# FeatherProto-V2_0.net
KiCad netlist of a schematic drawn in EAGLE
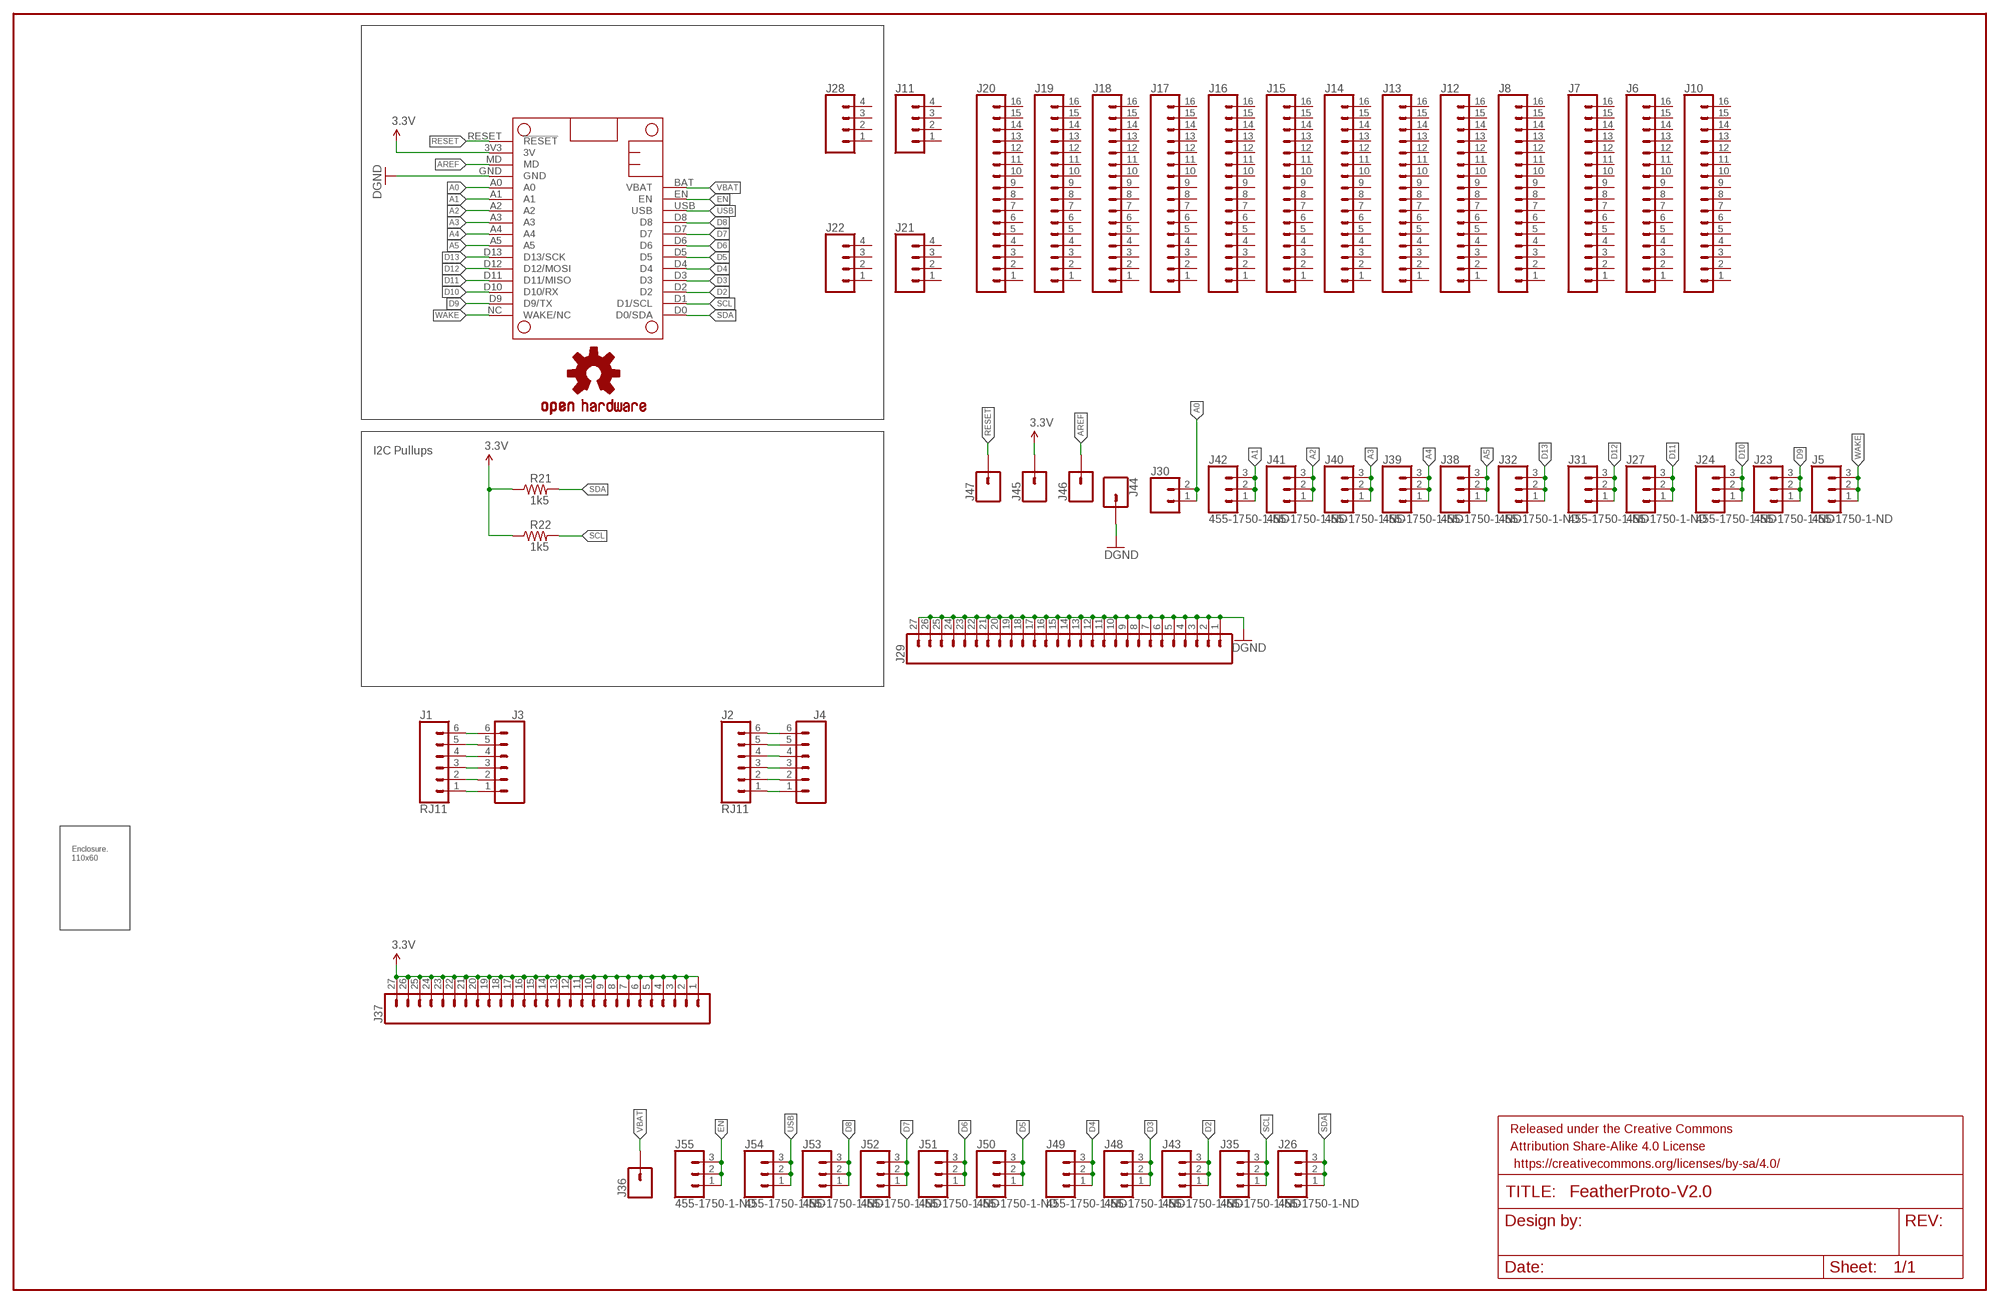
[diagram p0: schematic, sheet 1]

(export (version "E")
  (design (tool "Eeschema 10.0.6"))
  (components
    (comp (ref "FRAME2")
      (value "FRAME-LEDGER")
      (footprint "eagle-import:CREATIVE_COMMONS")
      (libsource (lib "eagle-import") (part "FRAME-LEDGER"))
    )
    (comp (ref "J1")
      (value "RJ11")
      (footprint "eagle-import:RJ11-6")
      (libsource (lib "eagle-import") (part "RJ11-6"))
    )
    (comp (ref "J2")
      (value "RJ11")
      (footprint "eagle-import:RJ11-6")
      (libsource (lib "eagle-import") (part "RJ11-6"))
    )
    (comp (ref "J3")
      (value "CONN_06SILK_FEMALE_PTH")
      (footprint "eagle-import:1X06")
      (libsource (lib "eagle-import") (part "CONN_06SILK_FEMALE_PTH"))
    )
    (comp (ref "J4")
      (value "CONN_06SILK_FEMALE_PTH")
      (footprint "eagle-import:1X06")
      (libsource (lib "eagle-import") (part "CONN_06SILK_FEMALE_PTH"))
    )
    (comp (ref "J5")
      (value "455-1750-1-ND")
      (footprint "eagle-import:1X03")
      (libsource (lib "eagle-import") (part "CONN_03"))
    )
    (comp (ref "J6")
      (value "CONN_161X16_NO_SILK")
      (footprint "eagle-import:1X16_NO_SILK")
      (libsource (lib "eagle-import") (part "CONN_161X16_NO_SILK"))
    )
    (comp (ref "J7")
      (value "CONN_161X16_NO_SILK")
      (footprint "eagle-import:1X16_NO_SILK")
      (libsource (lib "eagle-import") (part "CONN_161X16_NO_SILK"))
    )
    (comp (ref "J8")
      (value "CONN_161X16_NO_SILK")
      (footprint "eagle-import:1X16_NO_SILK")
      (libsource (lib "eagle-import") (part "CONN_161X16_NO_SILK"))
    )
    (comp (ref "J10")
      (value "CONN_161X16_NO_SILK")
      (footprint "eagle-import:1X16_NO_SILK")
      (libsource (lib "eagle-import") (part "CONN_161X16_NO_SILK"))
    )
    (comp (ref "J11")
      (value "CONN_041X04_NO_SILK")
      (footprint "eagle-import:1X04_NO_SILK")
      (libsource (lib "eagle-import") (part "CONN_041X04_NO_SILK"))
    )
    (comp (ref "J12")
      (value "CONN_161X16_NO_SILK")
      (footprint "eagle-import:1X16_NO_SILK")
      (libsource (lib "eagle-import") (part "CONN_161X16_NO_SILK"))
    )
    (comp (ref "J13")
      (value "CONN_161X16_NO_SILK")
      (footprint "eagle-import:1X16_NO_SILK")
      (libsource (lib "eagle-import") (part "CONN_161X16_NO_SILK"))
    )
    (comp (ref "J14")
      (value "CONN_161X16_NO_SILK")
      (footprint "eagle-import:1X16_NO_SILK")
      (libsource (lib "eagle-import") (part "CONN_161X16_NO_SILK"))
    )
    (comp (ref "J15")
      (value "CONN_161X16_NO_SILK")
      (footprint "eagle-import:1X16_NO_SILK")
      (libsource (lib "eagle-import") (part "CONN_161X16_NO_SILK"))
    )
    (comp (ref "J16")
      (value "CONN_161X16_NO_SILK")
      (footprint "eagle-import:1X16_NO_SILK")
      (libsource (lib "eagle-import") (part "CONN_161X16_NO_SILK"))
    )
    (comp (ref "J17")
      (value "CONN_161X16_NO_SILK")
      (footprint "eagle-import:1X16_NO_SILK")
      (libsource (lib "eagle-import") (part "CONN_161X16_NO_SILK"))
    )
    (comp (ref "J18")
      (value "CONN_161X16_NO_SILK")
      (footprint "eagle-import:1X16_NO_SILK")
      (libsource (lib "eagle-import") (part "CONN_161X16_NO_SILK"))
    )
    (comp (ref "J19")
      (value "CONN_161X16_NO_SILK")
      (footprint "eagle-import:1X16_NO_SILK")
      (libsource (lib "eagle-import") (part "CONN_161X16_NO_SILK"))
    )
    (comp (ref "J20")
      (value "CONN_161X16_NO_SILK")
      (footprint "eagle-import:1X16_NO_SILK")
      (libsource (lib "eagle-import") (part "CONN_161X16_NO_SILK"))
    )
    (comp (ref "J21")
      (value "CONN_041X04_NO_SILK")
      (footprint "eagle-import:1X04_NO_SILK")
      (libsource (lib "eagle-import") (part "CONN_041X04_NO_SILK"))
    )
    (comp (ref "J22")
      (value "CONN_041X04_NO_SILK")
      (footprint "eagle-import:1X04_NO_SILK")
      (libsource (lib "eagle-import") (part "CONN_041X04_NO_SILK"))
    )
    (comp (ref "J23")
      (value "455-1750-1-ND")
      (footprint "eagle-import:1X03")
      (libsource (lib "eagle-import") (part "CONN_03"))
    )
    (comp (ref "J24")
      (value "455-1750-1-ND")
      (footprint "eagle-import:1X03")
      (libsource (lib "eagle-import") (part "CONN_03"))
    )
    (comp (ref "J26")
      (value "455-1750-1-ND")
      (footprint "eagle-import:1X03")
      (libsource (lib "eagle-import") (part "CONN_03"))
    )
    (comp (ref "J27")
      (value "455-1750-1-ND")
      (footprint "eagle-import:1X03")
      (libsource (lib "eagle-import") (part "CONN_03"))
    )
    (comp (ref "J28")
      (value "CONN_041X04_NO_SILK")
      (footprint "eagle-import:1X04_NO_SILK")
      (libsource (lib "eagle-import") (part "CONN_041X04_NO_SILK"))
    )
    (comp (ref "J29")
      (value "CONN_27")
      (footprint "eagle-import:1X27")
      (libsource (lib "eagle-import") (part "CONN_27"))
    )
    (comp (ref "J30")
      (value "CONN_02")
      (footprint "eagle-import:1X02")
      (libsource (lib "eagle-import") (part "CONN_02"))
    )
    (comp (ref "J31")
      (value "455-1750-1-ND")
      (footprint "eagle-import:1X03")
      (libsource (lib "eagle-import") (part "CONN_03"))
    )
    (comp (ref "J32")
      (value "455-1750-1-ND")
      (footprint "eagle-import:1X03")
      (libsource (lib "eagle-import") (part "CONN_03"))
    )
    (comp (ref "J35")
      (value "455-1750-1-ND")
      (footprint "eagle-import:1X03")
      (libsource (lib "eagle-import") (part "CONN_03"))
    )
    (comp (ref "J36")
      (value "CONN_01PTH_NO_SILK_YES_STOP")
      (footprint "eagle-import:1X01_NO_SILK")
      (libsource (lib "eagle-import") (part "CONN_01PTH_NO_SILK_YES_STOP"))
    )
    (comp (ref "J37")
      (value "CONN_27")
      (footprint "eagle-import:1X27")
      (libsource (lib "eagle-import") (part "CONN_27"))
    )
    (comp (ref "J38")
      (value "455-1750-1-ND")
      (footprint "eagle-import:1X03")
      (libsource (lib "eagle-import") (part "CONN_03"))
    )
    (comp (ref "J39")
      (value "455-1750-1-ND")
      (footprint "eagle-import:1X03")
      (libsource (lib "eagle-import") (part "CONN_03"))
    )
    (comp (ref "J40")
      (value "455-1750-1-ND")
      (footprint "eagle-import:1X03")
      (libsource (lib "eagle-import") (part "CONN_03"))
    )
    (comp (ref "J41")
      (value "455-1750-1-ND")
      (footprint "eagle-import:1X03")
      (libsource (lib "eagle-import") (part "CONN_03"))
    )
    (comp (ref "J42")
      (value "455-1750-1-ND")
      (footprint "eagle-import:1X03")
      (libsource (lib "eagle-import") (part "CONN_03"))
    )
    (comp (ref "J43")
      (value "455-1750-1-ND")
      (footprint "eagle-import:1X03")
      (libsource (lib "eagle-import") (part "CONN_03"))
    )
    (comp (ref "J44")
      (value "CONN_01PTH_NO_SILK_YES_STOP")
      (footprint "eagle-import:1X01_NO_SILK")
      (libsource (lib "eagle-import") (part "CONN_01PTH_NO_SILK_YES_STOP"))
    )
    (comp (ref "J45")
      (value "CONN_01PTH_NO_SILK_YES_STOP")
      (footprint "eagle-import:1X01_NO_SILK")
      (libsource (lib "eagle-import") (part "CONN_01PTH_NO_SILK_YES_STOP"))
    )
    (comp (ref "J46")
      (value "CONN_01PTH_NO_SILK_YES_STOP")
      (footprint "eagle-import:1X01_NO_SILK")
      (libsource (lib "eagle-import") (part "CONN_01PTH_NO_SILK_YES_STOP"))
    )
    (comp (ref "J47")
      (value "CONN_01PTH_NO_SILK_YES_STOP")
      (footprint "eagle-import:1X01_NO_SILK")
      (libsource (lib "eagle-import") (part "CONN_01PTH_NO_SILK_YES_STOP"))
    )
    (comp (ref "J48")
      (value "455-1750-1-ND")
      (footprint "eagle-import:1X03")
      (libsource (lib "eagle-import") (part "CONN_03"))
    )
    (comp (ref "J49")
      (value "455-1750-1-ND")
      (footprint "eagle-import:1X03")
      (libsource (lib "eagle-import") (part "CONN_03"))
    )
    (comp (ref "J50")
      (value "455-1750-1-ND")
      (footprint "eagle-import:1X03")
      (libsource (lib "eagle-import") (part "CONN_03"))
    )
    (comp (ref "J51")
      (value "455-1750-1-ND")
      (footprint "eagle-import:1X03")
      (libsource (lib "eagle-import") (part "CONN_03"))
    )
    (comp (ref "J52")
      (value "455-1750-1-ND")
      (footprint "eagle-import:1X03")
      (libsource (lib "eagle-import") (part "CONN_03"))
    )
    (comp (ref "J53")
      (value "455-1750-1-ND")
      (footprint "eagle-import:1X03")
      (libsource (lib "eagle-import") (part "CONN_03"))
    )
    (comp (ref "J54")
      (value "455-1750-1-ND")
      (footprint "eagle-import:1X03")
      (libsource (lib "eagle-import") (part "CONN_03"))
    )
    (comp (ref "J55")
      (value "455-1750-1-ND")
      (footprint "eagle-import:1X03")
      (libsource (lib "eagle-import") (part "CONN_03"))
    )
    (comp (ref "LOGO1")
      (value "OSHW-LOGOM")
      (footprint "eagle-import:OSHW-LOGO-M")
      (libsource (lib "eagle-import") (part "OSHW-LOGOM"))
    )
    (comp (ref "MS1")
      (value "XENONA")
      (footprint "eagle-import:XENON_BREAKOUT_A")
      (libsource (lib "eagle-import") (part "XENONA"))
    )
    (comp (ref "R21")
      (value "1k5")
      (footprint "eagle-import:0805")
      (libsource (lib "eagle-import") (part "RESISTOR0805"))
    )
    (comp (ref "R22")
      (value "1k5")
      (footprint "eagle-import:0805")
      (libsource (lib "eagle-import") (part "RESISTOR0805"))
    )
    (comp (ref "U$1")
      (value "CAMDENBOSS-ENCLOSURE-110X60BOTH-EXTENDED-WIDE")
      (footprint "eagle-import:CAMDENBOSS_ENCLOSURE_110X60_WIDE_EXTENDED")
      (libsource (lib "eagle-import") (part "CAMDENBOSS-ENCLOSURE-110X60BOTH-EXTENDED-WIDE"))
    )
  )
  (nets
    (net (code "1") (name "3.3V") (class "Default")
      (node (ref "J37") (pin "1") (pinfunction "1_1") (pintype "passive"))
      (node (ref "J37") (pin "10") (pinfunction "10_10") (pintype "passive"))
      (node (ref "J37") (pin "11") (pinfunction "11_11") (pintype "passive"))
      (node (ref "J37") (pin "12") (pinfunction "12_12") (pintype "passive"))
      (node (ref "J37") (pin "13") (pinfunction "13_13") (pintype "passive"))
      (node (ref "J37") (pin "14") (pinfunction "14_14") (pintype "passive"))
      (node (ref "J37") (pin "15") (pinfunction "15_15") (pintype "passive"))
      (node (ref "J37") (pin "16") (pinfunction "16_16") (pintype "passive"))
      (node (ref "J37") (pin "17") (pinfunction "17_17") (pintype "passive"))
      (node (ref "J37") (pin "18") (pinfunction "18_18") (pintype "passive"))
      (node (ref "J37") (pin "19") (pinfunction "19_19") (pintype "passive"))
      (node (ref "J37") (pin "2") (pinfunction "2_2") (pintype "passive"))
      (node (ref "J37") (pin "20") (pinfunction "20_20") (pintype "passive"))
      (node (ref "J37") (pin "21") (pinfunction "21_21") (pintype "passive"))
      (node (ref "J37") (pin "22") (pinfunction "22_22") (pintype "passive"))
      (node (ref "J37") (pin "23") (pinfunction "23_23") (pintype "passive"))
      (node (ref "J37") (pin "24") (pinfunction "24_24") (pintype "passive"))
      (node (ref "J37") (pin "25") (pinfunction "25_25") (pintype "passive"))
      (node (ref "J37") (pin "26") (pinfunction "26_26") (pintype "passive"))
      (node (ref "J37") (pin "27") (pinfunction "27_27") (pintype "passive"))
      (node (ref "J37") (pin "3") (pinfunction "3_3") (pintype "passive"))
      (node (ref "J37") (pin "4") (pinfunction "4_4") (pintype "passive"))
      (node (ref "J37") (pin "5") (pinfunction "5_5") (pintype "passive"))
      (node (ref "J37") (pin "6") (pinfunction "6_6") (pintype "passive"))
      (node (ref "J37") (pin "7") (pinfunction "7_7") (pintype "passive"))
      (node (ref "J37") (pin "8") (pinfunction "8_8") (pintype "passive"))
      (node (ref "J37") (pin "9") (pinfunction "9_9") (pintype "passive"))
      (node (ref "J45") (pin "1") (pinfunction "1_1") (pintype "passive"))
      (node (ref "MS1") (pin "3V3") (pinfunction "3V_3V3") (pintype "power_in"))
      (node (ref "R21") (pin "1") (pinfunction "1_1") (pintype "passive"))
      (node (ref "R22") (pin "1") (pinfunction "1_1") (pintype "passive"))
    )
    (net (code "2") (name "A0") (class "Default")
      (node (ref "J30") (pin "1") (pinfunction "1_1") (pintype "passive"))
      (node (ref "J30") (pin "2") (pinfunction "2_2") (pintype "passive"))
      (node (ref "MS1") (pin "A0") (pinfunction "A0_A0") (pintype "bidirectional"))
    )
    (net (code "3") (name "A1") (class "Default")
      (node (ref "J42") (pin "1") (pinfunction "1_1") (pintype "passive"))
      (node (ref "J42") (pin "2") (pinfunction "2_2") (pintype "passive"))
      (node (ref "J42") (pin "3") (pinfunction "3_3") (pintype "passive"))
      (node (ref "MS1") (pin "A1") (pinfunction "A1_A1") (pintype "bidirectional"))
    )
    (net (code "4") (name "A2") (class "Default")
      (node (ref "J41") (pin "1") (pinfunction "1_1") (pintype "passive"))
      (node (ref "J41") (pin "2") (pinfunction "2_2") (pintype "passive"))
      (node (ref "J41") (pin "3") (pinfunction "3_3") (pintype "passive"))
      (node (ref "MS1") (pin "A2") (pinfunction "A2_A2") (pintype "bidirectional"))
    )
    (net (code "5") (name "A3") (class "Default")
      (node (ref "J40") (pin "1") (pinfunction "1_1") (pintype "passive"))
      (node (ref "J40") (pin "2") (pinfunction "2_2") (pintype "passive"))
      (node (ref "J40") (pin "3") (pinfunction "3_3") (pintype "passive"))
      (node (ref "MS1") (pin "A3") (pinfunction "A3_A3") (pintype "bidirectional"))
    )
    (net (code "6") (name "A4") (class "Default")
      (node (ref "J39") (pin "1") (pinfunction "1_1") (pintype "passive"))
      (node (ref "J39") (pin "2") (pinfunction "2_2") (pintype "passive"))
      (node (ref "J39") (pin "3") (pinfunction "3_3") (pintype "passive"))
      (node (ref "MS1") (pin "A4") (pinfunction "A4_A4") (pintype "bidirectional"))
    )
    (net (code "7") (name "A5") (class "Default")
      (node (ref "J38") (pin "1") (pinfunction "1_1") (pintype "passive"))
      (node (ref "J38") (pin "2") (pinfunction "2_2") (pintype "passive"))
      (node (ref "J38") (pin "3") (pinfunction "3_3") (pintype "passive"))
      (node (ref "MS1") (pin "A5") (pinfunction "A5_A5") (pintype "bidirectional"))
    )
    (net (code "8") (name "AREF") (class "Default")
      (node (ref "J46") (pin "1") (pinfunction "1_1") (pintype "passive"))
      (node (ref "MS1") (pin "MD") (pinfunction "MD_MD") (pintype "passive"))
    )
    (net (code "9") (name "D2") (class "Default")
      (node (ref "J43") (pin "1") (pinfunction "1_1") (pintype "passive"))
      (node (ref "J43") (pin "2") (pinfunction "2_2") (pintype "passive"))
      (node (ref "J43") (pin "3") (pinfunction "3_3") (pintype "passive"))
      (node (ref "MS1") (pin "D2") (pinfunction "D2_D2") (pintype "bidirectional"))
    )
    (net (code "10") (name "D3") (class "Default")
      (node (ref "J48") (pin "1") (pinfunction "1_1") (pintype "passive"))
      (node (ref "J48") (pin "2") (pinfunction "2_2") (pintype "passive"))
      (node (ref "J48") (pin "3") (pinfunction "3_3") (pintype "passive"))
      (node (ref "MS1") (pin "D3") (pinfunction "D3_D3") (pintype "bidirectional"))
    )
    (net (code "11") (name "D4") (class "Default")
      (node (ref "J49") (pin "1") (pinfunction "1_1") (pintype "passive"))
      (node (ref "J49") (pin "2") (pinfunction "2_2") (pintype "passive"))
      (node (ref "J49") (pin "3") (pinfunction "3_3") (pintype "passive"))
      (node (ref "MS1") (pin "D4") (pinfunction "D4_D4") (pintype "bidirectional"))
    )
    (net (code "12") (name "D5") (class "Default")
      (node (ref "J50") (pin "1") (pinfunction "1_1") (pintype "passive"))
      (node (ref "J50") (pin "2") (pinfunction "2_2") (pintype "passive"))
      (node (ref "J50") (pin "3") (pinfunction "3_3") (pintype "passive"))
      (node (ref "MS1") (pin "D5") (pinfunction "D5_D5") (pintype "bidirectional"))
    )
    (net (code "13") (name "D6") (class "Default")
      (node (ref "J51") (pin "1") (pinfunction "1_1") (pintype "passive"))
      (node (ref "J51") (pin "2") (pinfunction "2_2") (pintype "passive"))
      (node (ref "J51") (pin "3") (pinfunction "3_3") (pintype "passive"))
      (node (ref "MS1") (pin "D6") (pinfunction "D6_D6") (pintype "bidirectional"))
    )
    (net (code "14") (name "D7") (class "Default")
      (node (ref "J52") (pin "1") (pinfunction "1_1") (pintype "passive"))
      (node (ref "J52") (pin "2") (pinfunction "2_2") (pintype "passive"))
      (node (ref "J52") (pin "3") (pinfunction "3_3") (pintype "passive"))
      (node (ref "MS1") (pin "D7") (pinfunction "D7_D7") (pintype "bidirectional"))
    )
    (net (code "15") (name "D8") (class "Default")
      (node (ref "J53") (pin "1") (pinfunction "1_1") (pintype "passive"))
      (node (ref "J53") (pin "2") (pinfunction "2_2") (pintype "passive"))
      (node (ref "J53") (pin "3") (pinfunction "3_3") (pintype "passive"))
      (node (ref "MS1") (pin "D8") (pinfunction "D8_D8") (pintype "bidirectional"))
    )
    (net (code "16") (name "D9") (class "Default")
      (node (ref "J23") (pin "1") (pinfunction "1_1") (pintype "passive"))
      (node (ref "J23") (pin "2") (pinfunction "2_2") (pintype "passive"))
      (node (ref "J23") (pin "3") (pinfunction "3_3") (pintype "passive"))
      (node (ref "MS1") (pin "D9") (pinfunction "D9/TX_D9") (pintype "bidirectional"))
    )
    (net (code "17") (name "D10") (class "Default")
      (node (ref "J24") (pin "1") (pinfunction "1_1") (pintype "passive"))
      (node (ref "J24") (pin "2") (pinfunction "2_2") (pintype "passive"))
      (node (ref "J24") (pin "3") (pinfunction "3_3") (pintype "passive"))
      (node (ref "MS1") (pin "D10") (pinfunction "D10/RX_D10") (pintype "bidirectional"))
    )
    (net (code "18") (name "D11") (class "Default")
      (node (ref "J27") (pin "1") (pinfunction "1_1") (pintype "passive"))
      (node (ref "J27") (pin "2") (pinfunction "2_2") (pintype "passive"))
      (node (ref "J27") (pin "3") (pinfunction "3_3") (pintype "passive"))
      (node (ref "MS1") (pin "D11") (pinfunction "D11/MISO_D11") (pintype "bidirectional"))
    )
    (net (code "19") (name "D12") (class "Default")
      (node (ref "J31") (pin "1") (pinfunction "1_1") (pintype "passive"))
      (node (ref "J31") (pin "2") (pinfunction "2_2") (pintype "passive"))
      (node (ref "J31") (pin "3") (pinfunction "3_3") (pintype "passive"))
      (node (ref "MS1") (pin "D12") (pinfunction "D12/MOSI_D12") (pintype "bidirectional"))
    )
    (net (code "20") (name "D13") (class "Default")
      (node (ref "J32") (pin "1") (pinfunction "1_1") (pintype "passive"))
      (node (ref "J32") (pin "2") (pinfunction "2_2") (pintype "passive"))
      (node (ref "J32") (pin "3") (pinfunction "3_3") (pintype "passive"))
      (node (ref "MS1") (pin "D13") (pinfunction "D13/SCK_D13") (pintype "bidirectional"))
    )
    (net (code "21") (name "DGND") (class "Default")
      (node (ref "J29") (pin "1") (pinfunction "1_1") (pintype "passive"))
      (node (ref "J29") (pin "10") (pinfunction "10_10") (pintype "passive"))
      (node (ref "J29") (pin "11") (pinfunction "11_11") (pintype "passive"))
      (node (ref "J29") (pin "12") (pinfunction "12_12") (pintype "passive"))
      (node (ref "J29") (pin "13") (pinfunction "13_13") (pintype "passive"))
      (node (ref "J29") (pin "14") (pinfunction "14_14") (pintype "passive"))
      (node (ref "J29") (pin "15") (pinfunction "15_15") (pintype "passive"))
      (node (ref "J29") (pin "16") (pinfunction "16_16") (pintype "passive"))
      (node (ref "J29") (pin "17") (pinfunction "17_17") (pintype "passive"))
      (node (ref "J29") (pin "18") (pinfunction "18_18") (pintype "passive"))
      (node (ref "J29") (pin "19") (pinfunction "19_19") (pintype "passive"))
      (node (ref "J29") (pin "2") (pinfunction "2_2") (pintype "passive"))
      (node (ref "J29") (pin "20") (pinfunction "20_20") (pintype "passive"))
      (node (ref "J29") (pin "21") (pinfunction "21_21") (pintype "passive"))
      (node (ref "J29") (pin "22") (pinfunction "22_22") (pintype "passive"))
      (node (ref "J29") (pin "23") (pinfunction "23_23") (pintype "passive"))
      (node (ref "J29") (pin "24") (pinfunction "24_24") (pintype "passive"))
      (node (ref "J29") (pin "25") (pinfunction "25_25") (pintype "passive"))
      (node (ref "J29") (pin "26") (pinfunction "26_26") (pintype "passive"))
      (node (ref "J29") (pin "27") (pinfunction "27_27") (pintype "passive"))
      (node (ref "J29") (pin "3") (pinfunction "3_3") (pintype "passive"))
      (node (ref "J29") (pin "4") (pinfunction "4_4") (pintype "passive"))
      (node (ref "J29") (pin "5") (pinfunction "5_5") (pintype "passive"))
      (node (ref "J29") (pin "6") (pinfunction "6_6") (pintype "passive"))
      (node (ref "J29") (pin "7") (pinfunction "7_7") (pintype "passive"))
      (node (ref "J29") (pin "8") (pinfunction "8_8") (pintype "passive"))
      (node (ref "J29") (pin "9") (pinfunction "9_9") (pintype "passive"))
      (node (ref "J44") (pin "1") (pinfunction "1_1") (pintype "passive"))
      (node (ref "MS1") (pin "GND") (pinfunction "GND_GND") (pintype "power_in"))
    )
    (net (code "22") (name "EN") (class "Default")
      (node (ref "J55") (pin "1") (pinfunction "1_1") (pintype "passive"))
      (node (ref "J55") (pin "2") (pinfunction "2_2") (pintype "passive"))
      (node (ref "J55") (pin "3") (pinfunction "3_3") (pintype "passive"))
      (node (ref "MS1") (pin "EN") (pinfunction "EN_EN") (pintype "passive"))
    )
    (net (code "23") (name "Net-(J1-Pad1)") (class "Default")
      (node (ref "J1") (pin "1") (pinfunction "1_1") (pintype "passive"))
      (node (ref "J3") (pin "1") (pinfunction "1_1") (pintype "passive"))
    )
    (net (code "24") (name "Net-(J1-Pad2)") (class "Default")
      (node (ref "J1") (pin "2") (pinfunction "2_2") (pintype "passive"))
      (node (ref "J3") (pin "2") (pinfunction "2_2") (pintype "passive"))
    )
    (net (code "25") (name "Net-(J1-Pad3)") (class "Default")
      (node (ref "J1") (pin "3") (pinfunction "3_3") (pintype "passive"))
      (node (ref "J3") (pin "3") (pinfunction "3_3") (pintype "passive"))
    )
    (net (code "26") (name "Net-(J1-Pad4)") (class "Default")
      (node (ref "J1") (pin "4") (pinfunction "4_4") (pintype "passive"))
      (node (ref "J3") (pin "4") (pinfunction "4_4") (pintype "passive"))
    )
    (net (code "27") (name "Net-(J1-Pad5)") (class "Default")
      (node (ref "J1") (pin "5") (pinfunction "5_5") (pintype "passive"))
      (node (ref "J3") (pin "5") (pinfunction "5_5") (pintype "passive"))
    )
    (net (code "28") (name "Net-(J1-Pad6)") (class "Default")
      (node (ref "J1") (pin "6") (pinfunction "6_6") (pintype "passive"))
      (node (ref "J3") (pin "6") (pinfunction "6_6") (pintype "passive"))
    )
    (net (code "29") (name "Net-(J2-Pad1)") (class "Default")
      (node (ref "J2") (pin "1") (pinfunction "1_1") (pintype "passive"))
      (node (ref "J4") (pin "1") (pinfunction "1_1") (pintype "passive"))
    )
    (net (code "30") (name "Net-(J2-Pad2)") (class "Default")
      (node (ref "J2") (pin "2") (pinfunction "2_2") (pintype "passive"))
      (node (ref "J4") (pin "2") (pinfunction "2_2") (pintype "passive"))
    )
    (net (code "31") (name "Net-(J2-Pad3)") (class "Default")
      (node (ref "J2") (pin "3") (pinfunction "3_3") (pintype "passive"))
      (node (ref "J4") (pin "3") (pinfunction "3_3") (pintype "passive"))
    )
    (net (code "32") (name "Net-(J2-Pad4)") (class "Default")
      (node (ref "J2") (pin "4") (pinfunction "4_4") (pintype "passive"))
      (node (ref "J4") (pin "4") (pinfunction "4_4") (pintype "passive"))
    )
    (net (code "33") (name "Net-(J2-Pad5)") (class "Default")
      (node (ref "J2") (pin "5") (pinfunction "5_5") (pintype "passive"))
      (node (ref "J4") (pin "5") (pinfunction "5_5") (pintype "passive"))
    )
    (net (code "34") (name "Net-(J2-Pad6)") (class "Default")
      (node (ref "J2") (pin "6") (pinfunction "6_6") (pintype "passive"))
      (node (ref "J4") (pin "6") (pinfunction "6_6") (pintype "passive"))
    )
    (net (code "35") (name "RESET") (class "Default")
      (node (ref "J47") (pin "1") (pinfunction "1_1") (pintype "passive"))
      (node (ref "MS1") (pin "RESET") (pinfunction "~{RESET}_RESET") (pintype "input"))
    )
    (net (code "36") (name "SCL") (class "Default")
      (node (ref "J35") (pin "1") (pinfunction "1_1") (pintype "passive"))
      (node (ref "J35") (pin "2") (pinfunction "2_2") (pintype "passive"))
      (node (ref "J35") (pin "3") (pinfunction "3_3") (pintype "passive"))
      (node (ref "MS1") (pin "D1") (pinfunction "D1/SCL_D1") (pintype "bidirectional"))
      (node (ref "R22") (pin "2") (pinfunction "2_2") (pintype "passive"))
    )
    (net (code "37") (name "SDA") (class "Default")
      (node (ref "J26") (pin "1") (pinfunction "1_1") (pintype "passive"))
      (node (ref "J26") (pin "2") (pinfunction "2_2") (pintype "passive"))
      (node (ref "J26") (pin "3") (pinfunction "3_3") (pintype "passive"))
      (node (ref "MS1") (pin "D0") (pinfunction "D0/SDA_D0") (pintype "bidirectional"))
      (node (ref "R21") (pin "2") (pinfunction "2_2") (pintype "passive"))
    )
    (net (code "38") (name "USB") (class "Default")
      (node (ref "J54") (pin "1") (pinfunction "1_1") (pintype "passive"))
      (node (ref "J54") (pin "2") (pinfunction "2_2") (pintype "passive"))
      (node (ref "J54") (pin "3") (pinfunction "3_3") (pintype "passive"))
      (node (ref "MS1") (pin "USB") (pinfunction "USB_USB") (pintype "power_in"))
    )
    (net (code "39") (name "VBAT") (class "Default")
      (node (ref "J36") (pin "1") (pinfunction "1_1") (pintype "passive"))
      (node (ref "MS1") (pin "BAT") (pinfunction "VBAT_BAT") (pintype "power_in"))
    )
    (net (code "40") (name "WAKE") (class "Default")
      (node (ref "J5") (pin "1") (pinfunction "1_1") (pintype "passive"))
      (node (ref "J5") (pin "2") (pinfunction "2_2") (pintype "passive"))
      (node (ref "J5") (pin "3") (pinfunction "3_3") (pintype "passive"))
      (node (ref "MS1") (pin "NC") (pinfunction "WAKE/NC_NC") (pintype "passive"))
    )
    (net (code "41") (name "unconnected-(J6-Pad1)") (class "Default")
      (node (ref "J6") (pin "1") (pinfunction "1_1") (pintype "passive"))
    )
    (net (code "42") (name "unconnected-(J6-Pad2)") (class "Default")
      (node (ref "J6") (pin "2") (pinfunction "2_2") (pintype "passive"))
    )
    (net (code "43") (name "unconnected-(J6-Pad3)") (class "Default")
      (node (ref "J6") (pin "3") (pinfunction "3_3") (pintype "passive"))
    )
    (net (code "44") (name "unconnected-(J6-Pad4)") (class "Default")
      (node (ref "J6") (pin "4") (pinfunction "4_4") (pintype "passive"))
    )
    (net (code "45") (name "unconnected-(J6-Pad5)") (class "Default")
      (node (ref "J6") (pin "5") (pinfunction "5_5") (pintype "passive"))
    )
    (net (code "46") (name "unconnected-(J6-Pad6)") (class "Default")
      (node (ref "J6") (pin "6") (pinfunction "6_6") (pintype "passive"))
    )
    (net (code "47") (name "unconnected-(J6-Pad7)") (class "Default")
      (node (ref "J6") (pin "7") (pinfunction "7_7") (pintype "passive"))
    )
    (net (code "48") (name "unconnected-(J6-Pad8)") (class "Default")
      (node (ref "J6") (pin "8") (pinfunction "8_8") (pintype "passive"))
    )
    (net (code "49") (name "unconnected-(J6-Pad9)") (class "Default")
      (node (ref "J6") (pin "9") (pinfunction "9_9") (pintype "passive"))
    )
    (net (code "50") (name "unconnected-(J6-Pad10)") (class "Default")
      (node (ref "J6") (pin "10") (pinfunction "10_10") (pintype "passive"))
    )
    (net (code "51") (name "unconnected-(J6-Pad11)") (class "Default")
      (node (ref "J6") (pin "11") (pinfunction "11_11") (pintype "passive"))
    )
    (net (code "52") (name "unconnected-(J6-Pad12)") (class "Default")
      (node (ref "J6") (pin "12") (pinfunction "12_12") (pintype "passive"))
    )
    (net (code "53") (name "unconnected-(J6-Pad13)") (class "Default")
      (node (ref "J6") (pin "13") (pinfunction "13_13") (pintype "passive"))
    )
    (net (code "54") (name "unconnected-(J6-Pad14)") (class "Default")
      (node (ref "J6") (pin "14") (pinfunction "14_14") (pintype "passive"))
    )
    (net (code "55") (name "unconnected-(J6-Pad15)") (class "Default")
      (node (ref "J6") (pin "15") (pinfunction "15_15") (pintype "passive"))
    )
    (net (code "56") (name "unconnected-(J6-Pad16)") (class "Default")
      (node (ref "J6") (pin "16") (pinfunction "16_16") (pintype "passive"))
    )
    (net (code "57") (name "unconnected-(J7-Pad1)") (class "Default")
      (node (ref "J7") (pin "1") (pinfunction "1_1") (pintype "passive"))
    )
    (net (code "58") (name "unconnected-(J7-Pad2)") (class "Default")
      (node (ref "J7") (pin "2") (pinfunction "2_2") (pintype "passive"))
    )
    (net (code "59") (name "unconnected-(J7-Pad3)") (class "Default")
      (node (ref "J7") (pin "3") (pinfunction "3_3") (pintype "passive"))
    )
    (net (code "60") (name "unconnected-(J7-Pad4)") (class "Default")
      (node (ref "J7") (pin "4") (pinfunction "4_4") (pintype "passive"))
    )
    (net (code "61") (name "unconnected-(J7-Pad5)") (class "Default")
      (node (ref "J7") (pin "5") (pinfunction "5_5") (pintype "passive"))
    )
    (net (code "62") (name "unconnected-(J7-Pad6)") (class "Default")
      (node (ref "J7") (pin "6") (pinfunction "6_6") (pintype "passive"))
    )
    (net (code "63") (name "unconnected-(J7-Pad7)") (class "Default")
      (node (ref "J7") (pin "7") (pinfunction "7_7") (pintype "passive"))
    )
    (net (code "64") (name "unconnected-(J7-Pad8)") (class "Default")
      (node (ref "J7") (pin "8") (pinfunction "8_8") (pintype "passive"))
    )
    (net (code "65") (name "unconnected-(J7-Pad9)") (class "Default")
      (node (ref "J7") (pin "9") (pinfunction "9_9") (pintype "passive"))
    )
    (net (code "66") (name "unconnected-(J7-Pad10)") (class "Default")
      (node (ref "J7") (pin "10") (pinfunction "10_10") (pintype "passive"))
    )
    (net (code "67") (name "unconnected-(J7-Pad11)") (class "Default")
      (node (ref "J7") (pin "11") (pinfunction "11_11") (pintype "passive"))
    )
    (net (code "68") (name "unconnected-(J7-Pad12)") (class "Default")
      (node (ref "J7") (pin "12") (pinfunction "12_12") (pintype "passive"))
    )
    (net (code "69") (name "unconnected-(J7-Pad13)") (class "Default")
      (node (ref "J7") (pin "13") (pinfunction "13_13") (pintype "passive"))
    )
    (net (code "70") (name "unconnected-(J7-Pad14)") (class "Default")
      (node (ref "J7") (pin "14") (pinfunction "14_14") (pintype "passive"))
    )
    (net (code "71") (name "unconnected-(J7-Pad15)") (class "Default")
      (node (ref "J7") (pin "15") (pinfunction "15_15") (pintype "passive"))
    )
    (net (code "72") (name "unconnected-(J7-Pad16)") (class "Default")
      (node (ref "J7") (pin "16") (pinfunction "16_16") (pintype "passive"))
    )
    (net (code "73") (name "unconnected-(J8-Pad1)") (class "Default")
      (node (ref "J8") (pin "1") (pinfunction "1_1") (pintype "passive"))
    )
    (net (code "74") (name "unconnected-(J8-Pad2)") (class "Default")
      (node (ref "J8") (pin "2") (pinfunction "2_2") (pintype "passive"))
    )
    (net (code "75") (name "unconnected-(J8-Pad3)") (class "Default")
      (node (ref "J8") (pin "3") (pinfunction "3_3") (pintype "passive"))
    )
    (net (code "76") (name "unconnected-(J8-Pad4)") (class "Default")
      (node (ref "J8") (pin "4") (pinfunction "4_4") (pintype "passive"))
    )
    (net (code "77") (name "unconnected-(J8-Pad5)") (class "Default")
      (node (ref "J8") (pin "5") (pinfunction "5_5") (pintype "passive"))
    )
    (net (code "78") (name "unconnected-(J8-Pad6)") (class "Default")
      (node (ref "J8") (pin "6") (pinfunction "6_6") (pintype "passive"))
    )
    (net (code "79") (name "unconnected-(J8-Pad7)") (class "Default")
      (node (ref "J8") (pin "7") (pinfunction "7_7") (pintype "passive"))
    )
    (net (code "80") (name "unconnected-(J8-Pad8)") (class "Default")
      (node (ref "J8") (pin "8") (pinfunction "8_8") (pintype "passive"))
    )
    (net (code "81") (name "unconnected-(J8-Pad9)") (class "Default")
      (node (ref "J8") (pin "9") (pinfunction "9_9") (pintype "passive"))
    )
    (net (code "82") (name "unconnected-(J8-Pad10)") (class "Default")
      (node (ref "J8") (pin "10") (pinfunction "10_10") (pintype "passive"))
    )
    (net (code "83") (name "unconnected-(J8-Pad11)") (class "Default")
      (node (ref "J8") (pin "11") (pinfunction "11_11") (pintype "passive"))
    )
    (net (code "84") (name "unconnected-(J8-Pad12)") (class "Default")
      (node (ref "J8") (pin "12") (pinfunction "12_12") (pintype "passive"))
    )
    (net (code "85") (name "unconnected-(J8-Pad13)") (class "Default")
      (node (ref "J8") (pin "13") (pinfunction "13_13") (pintype "passive"))
    )
    (net (code "86") (name "unconnected-(J8-Pad14)") (class "Default")
      (node (ref "J8") (pin "14") (pinfunction "14_14") (pintype "passive"))
    )
    (net (code "87") (name "unconnected-(J8-Pad15)") (class "Default")
      (node (ref "J8") (pin "15") (pinfunction "15_15") (pintype "passive"))
    )
    (net (code "88") (name "unconnected-(J8-Pad16)") (class "Default")
      (node (ref "J8") (pin "16") (pinfunction "16_16") (pintype "passive"))
    )
    (net (code "89") (name "unconnected-(J10-Pad1)") (class "Default")
      (node (ref "J10") (pin "1") (pinfunction "1_1") (pintype "passive"))
    )
    (net (code "90") (name "unconnected-(J10-Pad2)") (class "Default")
      (node (ref "J10") (pin "2") (pinfunction "2_2") (pintype "passive"))
    )
    (net (code "91") (name "unconnected-(J10-Pad3)") (class "Default")
      (node (ref "J10") (pin "3") (pinfunction "3_3") (pintype "passive"))
    )
    (net (code "92") (name "unconnected-(J10-Pad4)") (class "Default")
      (node (ref "J10") (pin "4") (pinfunction "4_4") (pintype "passive"))
    )
    (net (code "93") (name "unconnected-(J10-Pad5)") (class "Default")
      (node (ref "J10") (pin "5") (pinfunction "5_5") (pintype "passive"))
    )
    (net (code "94") (name "unconnected-(J10-Pad6)") (class "Default")
      (node (ref "J10") (pin "6") (pinfunction "6_6") (pintype "passive"))
    )
    (net (code "95") (name "unconnected-(J10-Pad7)") (class "Default")
      (node (ref "J10") (pin "7") (pinfunction "7_7") (pintype "passive"))
    )
    (net (code "96") (name "unconnected-(J10-Pad8)") (class "Default")
      (node (ref "J10") (pin "8") (pinfunction "8_8") (pintype "passive"))
    )
    (net (code "97") (name "unconnected-(J10-Pad9)") (class "Default")
      (node (ref "J10") (pin "9") (pinfunction "9_9") (pintype "passive"))
    )
    (net (code "98") (name "unconnected-(J10-Pad10)") (class "Default")
      (node (ref "J10") (pin "10") (pinfunction "10_10") (pintype "passive"))
    )
    (net (code "99") (name "unconnected-(J10-Pad11)") (class "Default")
      (node (ref "J10") (pin "11") (pinfunction "11_11") (pintype "passive"))
    )
    (net (code "100") (name "unconnected-(J10-Pad12)") (class "Default")
      (node (ref "J10") (pin "12") (pinfunction "12_12") (pintype "passive"))
    )
    (net (code "101") (name "unconnected-(J10-Pad13)") (class "Default")
      (node (ref "J10") (pin "13") (pinfunction "13_13") (pintype "passive"))
    )
    (net (code "102") (name "unconnected-(J10-Pad14)") (class "Default")
      (node (ref "J10") (pin "14") (pinfunction "14_14") (pintype "passive"))
    )
    (net (code "103") (name "unconnected-(J10-Pad15)") (class "Default")
      (node (ref "J10") (pin "15") (pinfunction "15_15") (pintype "passive"))
    )
    (net (code "104") (name "unconnected-(J10-Pad16)") (class "Default")
      (node (ref "J10") (pin "16") (pinfunction "16_16") (pintype "passive"))
    )
    (net (code "105") (name "unconnected-(J11-Pad1)") (class "Default")
      (node (ref "J11") (pin "1") (pinfunction "1_1") (pintype "passive"))
    )
    (net (code "106") (name "unconnected-(J11-Pad2)") (class "Default")
      (node (ref "J11") (pin "2") (pinfunction "2_2") (pintype "passive"))
    )
    (net (code "107") (name "unconnected-(J11-Pad3)") (class "Default")
      (node (ref "J11") (pin "3") (pinfunction "3_3") (pintype "passive"))
    )
    (net (code "108") (name "unconnected-(J11-Pad4)") (class "Default")
      (node (ref "J11") (pin "4") (pinfunction "4_4") (pintype "passive"))
    )
    (net (code "109") (name "unconnected-(J12-Pad1)") (class "Default")
      (node (ref "J12") (pin "1") (pinfunction "1_1") (pintype "passive"))
    )
    (net (code "110") (name "unconnected-(J12-Pad2)") (class "Default")
      (node (ref "J12") (pin "2") (pinfunction "2_2") (pintype "passive"))
    )
    (net (code "111") (name "unconnected-(J12-Pad3)") (class "Default")
      (node (ref "J12") (pin "3") (pinfunction "3_3") (pintype "passive"))
    )
    (net (code "112") (name "unconnected-(J12-Pad4)") (class "Default")
      (node (ref "J12") (pin "4") (pinfunction "4_4") (pintype "passive"))
    )
    (net (code "113") (name "unconnected-(J12-Pad5)") (class "Default")
      (node (ref "J12") (pin "5") (pinfunction "5_5") (pintype "passive"))
    )
    (net (code "114") (name "unconnected-(J12-Pad6)") (class "Default")
      (node (ref "J12") (pin "6") (pinfunction "6_6") (pintype "passive"))
    )
    (net (code "115") (name "unconnected-(J12-Pad7)") (class "Default")
      (node (ref "J12") (pin "7") (pinfunction "7_7") (pintype "passive"))
    )
    (net (code "116") (name "unconnected-(J12-Pad8)") (class "Default")
      (node (ref "J12") (pin "8") (pinfunction "8_8") (pintype "passive"))
    )
    (net (code "117") (name "unconnected-(J12-Pad9)") (class "Default")
      (node (ref "J12") (pin "9") (pinfunction "9_9") (pintype "passive"))
    )
    (net (code "118") (name "unconnected-(J12-Pad10)") (class "Default")
      (node (ref "J12") (pin "10") (pinfunction "10_10") (pintype "passive"))
    )
    (net (code "119") (name "unconnected-(J12-Pad11)") (class "Default")
      (node (ref "J12") (pin "11") (pinfunction "11_11") (pintype "passive"))
    )
    (net (code "120") (name "unconnected-(J12-Pad12)") (class "Default")
      (node (ref "J12") (pin "12") (pinfunction "12_12") (pintype "passive"))
    )
    (net (code "121") (name "unconnected-(J12-Pad13)") (class "Default")
      (node (ref "J12") (pin "13") (pinfunction "13_13") (pintype "passive"))
    )
    (net (code "122") (name "unconnected-(J12-Pad14)") (class "Default")
      (node (ref "J12") (pin "14") (pinfunction "14_14") (pintype "passive"))
    )
    (net (code "123") (name "unconnected-(J12-Pad15)") (class "Default")
      (node (ref "J12") (pin "15") (pinfunction "15_15") (pintype "passive"))
    )
    (net (code "124") (name "unconnected-(J12-Pad16)") (class "Default")
      (node (ref "J12") (pin "16") (pinfunction "16_16") (pintype "passive"))
    )
    (net (code "125") (name "unconnected-(J13-Pad1)") (class "Default")
      (node (ref "J13") (pin "1") (pinfunction "1_1") (pintype "passive"))
    )
    (net (code "126") (name "unconnected-(J13-Pad2)") (class "Default")
      (node (ref "J13") (pin "2") (pinfunction "2_2") (pintype "passive"))
    )
    (net (code "127") (name "unconnected-(J13-Pad3)") (class "Default")
      (node (ref "J13") (pin "3") (pinfunction "3_3") (pintype "passive"))
    )
    (net (code "128") (name "unconnected-(J13-Pad4)") (class "Default")
      (node (ref "J13") (pin "4") (pinfunction "4_4") (pintype "passive"))
    )
    (net (code "129") (name "unconnected-(J13-Pad5)") (class "Default")
      (node (ref "J13") (pin "5") (pinfunction "5_5") (pintype "passive"))
    )
    (net (code "130") (name "unconnected-(J13-Pad6)") (class "Default")
      (node (ref "J13") (pin "6") (pinfunction "6_6") (pintype "passive"))
    )
    (net (code "131") (name "unconnected-(J13-Pad7)") (class "Default")
      (node (ref "J13") (pin "7") (pinfunction "7_7") (pintype "passive"))
    )
    (net (code "132") (name "unconnected-(J13-Pad8)") (class "Default")
      (node (ref "J13") (pin "8") (pinfunction "8_8") (pintype "passive"))
    )
    (net (code "133") (name "unconnected-(J13-Pad9)") (class "Default")
      (node (ref "J13") (pin "9") (pinfunction "9_9") (pintype "passive"))
    )
    (net (code "134") (name "unconnected-(J13-Pad10)") (class "Default")
      (node (ref "J13") (pin "10") (pinfunction "10_10") (pintype "passive"))
    )
    (net (code "135") (name "unconnected-(J13-Pad11)") (class "Default")
      (node (ref "J13") (pin "11") (pinfunction "11_11") (pintype "passive"))
    )
    (net (code "136") (name "unconnected-(J13-Pad12)") (class "Default")
      (node (ref "J13") (pin "12") (pinfunction "12_12") (pintype "passive"))
    )
    (net (code "137") (name "unconnected-(J13-Pad13)") (class "Default")
      (node (ref "J13") (pin "13") (pinfunction "13_13") (pintype "passive"))
    )
    (net (code "138") (name "unconnected-(J13-Pad14)") (class "Default")
      (node (ref "J13") (pin "14") (pinfunction "14_14") (pintype "passive"))
    )
    (net (code "139") (name "unconnected-(J13-Pad15)") (class "Default")
      (node (ref "J13") (pin "15") (pinfunction "15_15") (pintype "passive"))
    )
    (net (code "140") (name "unconnected-(J13-Pad16)") (class "Default")
      (node (ref "J13") (pin "16") (pinfunction "16_16") (pintype "passive"))
    )
    (net (code "141") (name "unconnected-(J14-Pad1)") (class "Default")
      (node (ref "J14") (pin "1") (pinfunction "1_1") (pintype "passive"))
    )
    (net (code "142") (name "unconnected-(J14-Pad2)") (class "Default")
      (node (ref "J14") (pin "2") (pinfunction "2_2") (pintype "passive"))
    )
    (net (code "143") (name "unconnected-(J14-Pad3)") (class "Default")
      (node (ref "J14") (pin "3") (pinfunction "3_3") (pintype "passive"))
    )
    (net (code "144") (name "unconnected-(J14-Pad4)") (class "Default")
      (node (ref "J14") (pin "4") (pinfunction "4_4") (pintype "passive"))
    )
    (net (code "145") (name "unconnected-(J14-Pad5)") (class "Default")
      (node (ref "J14") (pin "5") (pinfunction "5_5") (pintype "passive"))
    )
    (net (code "146") (name "unconnected-(J14-Pad6)") (class "Default")
      (node (ref "J14") (pin "6") (pinfunction "6_6") (pintype "passive"))
    )
    (net (code "147") (name "unconnected-(J14-Pad7)") (class "Default")
      (node (ref "J14") (pin "7") (pinfunction "7_7") (pintype "passive"))
    )
    (net (code "148") (name "unconnected-(J14-Pad8)") (class "Default")
      (node (ref "J14") (pin "8") (pinfunction "8_8") (pintype "passive"))
    )
    (net (code "149") (name "unconnected-(J14-Pad9)") (class "Default")
      (node (ref "J14") (pin "9") (pinfunction "9_9") (pintype "passive"))
    )
    (net (code "150") (name "unconnected-(J14-Pad10)") (class "Default")
      (node (ref "J14") (pin "10") (pinfunction "10_10") (pintype "passive"))
    )
    (net (code "151") (name "unconnected-(J14-Pad11)") (class "Default")
      (node (ref "J14") (pin "11") (pinfunction "11_11") (pintype "passive"))
    )
    (net (code "152") (name "unconnected-(J14-Pad12)") (class "Default")
      (node (ref "J14") (pin "12") (pinfunction "12_12") (pintype "passive"))
    )
    (net (code "153") (name "unconnected-(J14-Pad13)") (class "Default")
      (node (ref "J14") (pin "13") (pinfunction "13_13") (pintype "passive"))
    )
    (net (code "154") (name "unconnected-(J14-Pad14)") (class "Default")
      (node (ref "J14") (pin "14") (pinfunction "14_14") (pintype "passive"))
    )
    (net (code "155") (name "unconnected-(J14-Pad15)") (class "Default")
      (node (ref "J14") (pin "15") (pinfunction "15_15") (pintype "passive"))
    )
    (net (code "156") (name "unconnected-(J14-Pad16)") (class "Default")
      (node (ref "J14") (pin "16") (pinfunction "16_16") (pintype "passive"))
    )
    (net (code "157") (name "unconnected-(J15-Pad1)") (class "Default")
      (node (ref "J15") (pin "1") (pinfunction "1_1") (pintype "passive"))
    )
    (net (code "158") (name "unconnected-(J15-Pad2)") (class "Default")
      (node (ref "J15") (pin "2") (pinfunction "2_2") (pintype "passive"))
    )
    (net (code "159") (name "unconnected-(J15-Pad3)") (class "Default")
      (node (ref "J15") (pin "3") (pinfunction "3_3") (pintype "passive"))
    )
    (net (code "160") (name "unconnected-(J15-Pad4)") (class "Default")
      (node (ref "J15") (pin "4") (pinfunction "4_4") (pintype "passive"))
    )
    (net (code "161") (name "unconnected-(J15-Pad5)") (class "Default")
      (node (ref "J15") (pin "5") (pinfunction "5_5") (pintype "passive"))
    )
    (net (code "162") (name "unconnected-(J15-Pad6)") (class "Default")
      (node (ref "J15") (pin "6") (pinfunction "6_6") (pintype "passive"))
    )
    (net (code "163") (name "unconnected-(J15-Pad7)") (class "Default")
      (node (ref "J15") (pin "7") (pinfunction "7_7") (pintype "passive"))
    )
    (net (code "164") (name "unconnected-(J15-Pad8)") (class "Default")
      (node (ref "J15") (pin "8") (pinfunction "8_8") (pintype "passive"))
    )
    (net (code "165") (name "unconnected-(J15-Pad9)") (class "Default")
      (node (ref "J15") (pin "9") (pinfunction "9_9") (pintype "passive"))
    )
    (net (code "166") (name "unconnected-(J15-Pad10)") (class "Default")
      (node (ref "J15") (pin "10") (pinfunction "10_10") (pintype "passive"))
    )
    (net (code "167") (name "unconnected-(J15-Pad11)") (class "Default")
      (node (ref "J15") (pin "11") (pinfunction "11_11") (pintype "passive"))
    )
    (net (code "168") (name "unconnected-(J15-Pad12)") (class "Default")
      (node (ref "J15") (pin "12") (pinfunction "12_12") (pintype "passive"))
    )
    (net (code "169") (name "unconnected-(J15-Pad13)") (class "Default")
      (node (ref "J15") (pin "13") (pinfunction "13_13") (pintype "passive"))
    )
    (net (code "170") (name "unconnected-(J15-Pad14)") (class "Default")
      (node (ref "J15") (pin "14") (pinfunction "14_14") (pintype "passive"))
    )
    (net (code "171") (name "unconnected-(J15-Pad15)") (class "Default")
      (node (ref "J15") (pin "15") (pinfunction "15_15") (pintype "passive"))
    )
    (net (code "172") (name "unconnected-(J15-Pad16)") (class "Default")
      (node (ref "J15") (pin "16") (pinfunction "16_16") (pintype "passive"))
    )
    (net (code "173") (name "unconnected-(J16-Pad1)") (class "Default")
      (node (ref "J16") (pin "1") (pinfunction "1_1") (pintype "passive"))
    )
    (net (code "174") (name "unconnected-(J16-Pad2)") (class "Default")
      (node (ref "J16") (pin "2") (pinfunction "2_2") (pintype "passive"))
    )
    (net (code "175") (name "unconnected-(J16-Pad3)") (class "Default")
      (node (ref "J16") (pin "3") (pinfunction "3_3") (pintype "passive"))
    )
    (net (code "176") (name "unconnected-(J16-Pad4)") (class "Default")
      (node (ref "J16") (pin "4") (pinfunction "4_4") (pintype "passive"))
    )
    (net (code "177") (name "unconnected-(J16-Pad5)") (class "Default")
      (node (ref "J16") (pin "5") (pinfunction "5_5") (pintype "passive"))
    )
    (net (code "178") (name "unconnected-(J16-Pad6)") (class "Default")
      (node (ref "J16") (pin "6") (pinfunction "6_6") (pintype "passive"))
    )
    (net (code "179") (name "unconnected-(J16-Pad7)") (class "Default")
      (node (ref "J16") (pin "7") (pinfunction "7_7") (pintype "passive"))
    )
    (net (code "180") (name "unconnected-(J16-Pad8)") (class "Default")
      (node (ref "J16") (pin "8") (pinfunction "8_8") (pintype "passive"))
    )
    (net (code "181") (name "unconnected-(J16-Pad9)") (class "Default")
      (node (ref "J16") (pin "9") (pinfunction "9_9") (pintype "passive"))
    )
    (net (code "182") (name "unconnected-(J16-Pad10)") (class "Default")
      (node (ref "J16") (pin "10") (pinfunction "10_10") (pintype "passive"))
    )
    (net (code "183") (name "unconnected-(J16-Pad11)") (class "Default")
      (node (ref "J16") (pin "11") (pinfunction "11_11") (pintype "passive"))
    )
    (net (code "184") (name "unconnected-(J16-Pad12)") (class "Default")
      (node (ref "J16") (pin "12") (pinfunction "12_12") (pintype "passive"))
    )
    (net (code "185") (name "unconnected-(J16-Pad13)") (class "Default")
      (node (ref "J16") (pin "13") (pinfunction "13_13") (pintype "passive"))
    )
    (net (code "186") (name "unconnected-(J16-Pad14)") (class "Default")
      (node (ref "J16") (pin "14") (pinfunction "14_14") (pintype "passive"))
    )
    (net (code "187") (name "unconnected-(J16-Pad15)") (class "Default")
      (node (ref "J16") (pin "15") (pinfunction "15_15") (pintype "passive"))
    )
    (net (code "188") (name "unconnected-(J16-Pad16)") (class "Default")
      (node (ref "J16") (pin "16") (pinfunction "16_16") (pintype "passive"))
    )
    (net (code "189") (name "unconnected-(J17-Pad1)") (class "Default")
      (node (ref "J17") (pin "1") (pinfunction "1_1") (pintype "passive"))
    )
    (net (code "190") (name "unconnected-(J17-Pad2)") (class "Default")
      (node (ref "J17") (pin "2") (pinfunction "2_2") (pintype "passive"))
    )
    (net (code "191") (name "unconnected-(J17-Pad3)") (class "Default")
      (node (ref "J17") (pin "3") (pinfunction "3_3") (pintype "passive"))
    )
    (net (code "192") (name "unconnected-(J17-Pad4)") (class "Default")
      (node (ref "J17") (pin "4") (pinfunction "4_4") (pintype "passive"))
    )
    (net (code "193") (name "unconnected-(J17-Pad5)") (class "Default")
      (node (ref "J17") (pin "5") (pinfunction "5_5") (pintype "passive"))
    )
    (net (code "194") (name "unconnected-(J17-Pad6)") (class "Default")
      (node (ref "J17") (pin "6") (pinfunction "6_6") (pintype "passive"))
    )
    (net (code "195") (name "unconnected-(J17-Pad7)") (class "Default")
      (node (ref "J17") (pin "7") (pinfunction "7_7") (pintype "passive"))
    )
    (net (code "196") (name "unconnected-(J17-Pad8)") (class "Default")
      (node (ref "J17") (pin "8") (pinfunction "8_8") (pintype "passive"))
    )
    (net (code "197") (name "unconnected-(J17-Pad9)") (class "Default")
      (node (ref "J17") (pin "9") (pinfunction "9_9") (pintype "passive"))
    )
    (net (code "198") (name "unconnected-(J17-Pad10)") (class "Default")
      (node (ref "J17") (pin "10") (pinfunction "10_10") (pintype "passive"))
    )
    (net (code "199") (name "unconnected-(J17-Pad11)") (class "Default")
      (node (ref "J17") (pin "11") (pinfunction "11_11") (pintype "passive"))
    )
    (net (code "200") (name "unconnected-(J17-Pad12)") (class "Default")
      (node (ref "J17") (pin "12") (pinfunction "12_12") (pintype "passive"))
    )
    (net (code "201") (name "unconnected-(J17-Pad13)") (class "Default")
      (node (ref "J17") (pin "13") (pinfunction "13_13") (pintype "passive"))
    )
    (net (code "202") (name "unconnected-(J17-Pad14)") (class "Default")
      (node (ref "J17") (pin "14") (pinfunction "14_14") (pintype "passive"))
    )
    (net (code "203") (name "unconnected-(J17-Pad15)") (class "Default")
      (node (ref "J17") (pin "15") (pinfunction "15_15") (pintype "passive"))
    )
    (net (code "204") (name "unconnected-(J17-Pad16)") (class "Default")
      (node (ref "J17") (pin "16") (pinfunction "16_16") (pintype "passive"))
    )
    (net (code "205") (name "unconnected-(J18-Pad1)") (class "Default")
      (node (ref "J18") (pin "1") (pinfunction "1_1") (pintype "passive"))
    )
    (net (code "206") (name "unconnected-(J18-Pad2)") (class "Default")
      (node (ref "J18") (pin "2") (pinfunction "2_2") (pintype "passive"))
    )
    (net (code "207") (name "unconnected-(J18-Pad3)") (class "Default")
      (node (ref "J18") (pin "3") (pinfunction "3_3") (pintype "passive"))
    )
    (net (code "208") (name "unconnected-(J18-Pad4)") (class "Default")
      (node (ref "J18") (pin "4") (pinfunction "4_4") (pintype "passive"))
    )
    (net (code "209") (name "unconnected-(J18-Pad5)") (class "Default")
      (node (ref "J18") (pin "5") (pinfunction "5_5") (pintype "passive"))
    )
    (net (code "210") (name "unconnected-(J18-Pad6)") (class "Default")
      (node (ref "J18") (pin "6") (pinfunction "6_6") (pintype "passive"))
    )
    (net (code "211") (name "unconnected-(J18-Pad7)") (class "Default")
      (node (ref "J18") (pin "7") (pinfunction "7_7") (pintype "passive"))
    )
    (net (code "212") (name "unconnected-(J18-Pad8)") (class "Default")
      (node (ref "J18") (pin "8") (pinfunction "8_8") (pintype "passive"))
    )
    (net (code "213") (name "unconnected-(J18-Pad9)") (class "Default")
      (node (ref "J18") (pin "9") (pinfunction "9_9") (pintype "passive"))
    )
    (net (code "214") (name "unconnected-(J18-Pad10)") (class "Default")
      (node (ref "J18") (pin "10") (pinfunction "10_10") (pintype "passive"))
    )
    (net (code "215") (name "unconnected-(J18-Pad11)") (class "Default")
      (node (ref "J18") (pin "11") (pinfunction "11_11") (pintype "passive"))
    )
    (net (code "216") (name "unconnected-(J18-Pad12)") (class "Default")
      (node (ref "J18") (pin "12") (pinfunction "12_12") (pintype "passive"))
    )
    (net (code "217") (name "unconnected-(J18-Pad13)") (class "Default")
      (node (ref "J18") (pin "13") (pinfunction "13_13") (pintype "passive"))
    )
    (net (code "218") (name "unconnected-(J18-Pad14)") (class "Default")
      (node (ref "J18") (pin "14") (pinfunction "14_14") (pintype "passive"))
    )
    (net (code "219") (name "unconnected-(J18-Pad15)") (class "Default")
      (node (ref "J18") (pin "15") (pinfunction "15_15") (pintype "passive"))
    )
    (net (code "220") (name "unconnected-(J18-Pad16)") (class "Default")
      (node (ref "J18") (pin "16") (pinfunction "16_16") (pintype "passive"))
    )
    (net (code "221") (name "unconnected-(J19-Pad1)") (class "Default")
      (node (ref "J19") (pin "1") (pinfunction "1_1") (pintype "passive"))
    )
    (net (code "222") (name "unconnected-(J19-Pad2)") (class "Default")
      (node (ref "J19") (pin "2") (pinfunction "2_2") (pintype "passive"))
    )
    (net (code "223") (name "unconnected-(J19-Pad3)") (class "Default")
      (node (ref "J19") (pin "3") (pinfunction "3_3") (pintype "passive"))
    )
    (net (code "224") (name "unconnected-(J19-Pad4)") (class "Default")
      (node (ref "J19") (pin "4") (pinfunction "4_4") (pintype "passive"))
    )
    (net (code "225") (name "unconnected-(J19-Pad5)") (class "Default")
      (node (ref "J19") (pin "5") (pinfunction "5_5") (pintype "passive"))
    )
    (net (code "226") (name "unconnected-(J19-Pad6)") (class "Default")
      (node (ref "J19") (pin "6") (pinfunction "6_6") (pintype "passive"))
    )
    (net (code "227") (name "unconnected-(J19-Pad7)") (class "Default")
      (node (ref "J19") (pin "7") (pinfunction "7_7") (pintype "passive"))
    )
    (net (code "228") (name "unconnected-(J19-Pad8)") (class "Default")
      (node (ref "J19") (pin "8") (pinfunction "8_8") (pintype "passive"))
    )
    (net (code "229") (name "unconnected-(J19-Pad9)") (class "Default")
      (node (ref "J19") (pin "9") (pinfunction "9_9") (pintype "passive"))
    )
    (net (code "230") (name "unconnected-(J19-Pad10)") (class "Default")
      (node (ref "J19") (pin "10") (pinfunction "10_10") (pintype "passive"))
    )
    (net (code "231") (name "unconnected-(J19-Pad11)") (class "Default")
      (node (ref "J19") (pin "11") (pinfunction "11_11") (pintype "passive"))
    )
    (net (code "232") (name "unconnected-(J19-Pad12)") (class "Default")
      (node (ref "J19") (pin "12") (pinfunction "12_12") (pintype "passive"))
    )
    (net (code "233") (name "unconnected-(J19-Pad13)") (class "Default")
      (node (ref "J19") (pin "13") (pinfunction "13_13") (pintype "passive"))
    )
    (net (code "234") (name "unconnected-(J19-Pad14)") (class "Default")
      (node (ref "J19") (pin "14") (pinfunction "14_14") (pintype "passive"))
    )
    (net (code "235") (name "unconnected-(J19-Pad15)") (class "Default")
      (node (ref "J19") (pin "15") (pinfunction "15_15") (pintype "passive"))
    )
    (net (code "236") (name "unconnected-(J19-Pad16)") (class "Default")
      (node (ref "J19") (pin "16") (pinfunction "16_16") (pintype "passive"))
    )
    (net (code "237") (name "unconnected-(J20-Pad1)") (class "Default")
      (node (ref "J20") (pin "1") (pinfunction "1_1") (pintype "passive"))
    )
    (net (code "238") (name "unconnected-(J20-Pad2)") (class "Default")
      (node (ref "J20") (pin "2") (pinfunction "2_2") (pintype "passive"))
    )
    (net (code "239") (name "unconnected-(J20-Pad3)") (class "Default")
      (node (ref "J20") (pin "3") (pinfunction "3_3") (pintype "passive"))
    )
    (net (code "240") (name "unconnected-(J20-Pad4)") (class "Default")
      (node (ref "J20") (pin "4") (pinfunction "4_4") (pintype "passive"))
    )
    (net (code "241") (name "unconnected-(J20-Pad5)") (class "Default")
      (node (ref "J20") (pin "5") (pinfunction "5_5") (pintype "passive"))
    )
    (net (code "242") (name "unconnected-(J20-Pad6)") (class "Default")
      (node (ref "J20") (pin "6") (pinfunction "6_6") (pintype "passive"))
    )
    (net (code "243") (name "unconnected-(J20-Pad7)") (class "Default")
      (node (ref "J20") (pin "7") (pinfunction "7_7") (pintype "passive"))
    )
    (net (code "244") (name "unconnected-(J20-Pad8)") (class "Default")
      (node (ref "J20") (pin "8") (pinfunction "8_8") (pintype "passive"))
    )
    (net (code "245") (name "unconnected-(J20-Pad9)") (class "Default")
      (node (ref "J20") (pin "9") (pinfunction "9_9") (pintype "passive"))
    )
    (net (code "246") (name "unconnected-(J20-Pad10)") (class "Default")
      (node (ref "J20") (pin "10") (pinfunction "10_10") (pintype "passive"))
    )
    (net (code "247") (name "unconnected-(J20-Pad11)") (class "Default")
      (node (ref "J20") (pin "11") (pinfunction "11_11") (pintype "passive"))
    )
    (net (code "248") (name "unconnected-(J20-Pad12)") (class "Default")
      (node (ref "J20") (pin "12") (pinfunction "12_12") (pintype "passive"))
    )
    (net (code "249") (name "unconnected-(J20-Pad13)") (class "Default")
      (node (ref "J20") (pin "13") (pinfunction "13_13") (pintype "passive"))
    )
    (net (code "250") (name "unconnected-(J20-Pad14)") (class "Default")
      (node (ref "J20") (pin "14") (pinfunction "14_14") (pintype "passive"))
    )
    (net (code "251") (name "unconnected-(J20-Pad15)") (class "Default")
      (node (ref "J20") (pin "15") (pinfunction "15_15") (pintype "passive"))
    )
    (net (code "252") (name "unconnected-(J20-Pad16)") (class "Default")
      (node (ref "J20") (pin "16") (pinfunction "16_16") (pintype "passive"))
    )
    (net (code "253") (name "unconnected-(J21-Pad1)") (class "Default")
      (node (ref "J21") (pin "1") (pinfunction "1_1") (pintype "passive"))
    )
    (net (code "254") (name "unconnected-(J21-Pad2)") (class "Default")
      (node (ref "J21") (pin "2") (pinfunction "2_2") (pintype "passive"))
    )
    (net (code "255") (name "unconnected-(J21-Pad3)") (class "Default")
      (node (ref "J21") (pin "3") (pinfunction "3_3") (pintype "passive"))
    )
    (net (code "256") (name "unconnected-(J21-Pad4)") (class "Default")
      (node (ref "J21") (pin "4") (pinfunction "4_4") (pintype "passive"))
    )
    (net (code "257") (name "unconnected-(J22-Pad1)") (class "Default")
      (node (ref "J22") (pin "1") (pinfunction "1_1") (pintype "passive"))
    )
    (net (code "258") (name "unconnected-(J22-Pad2)") (class "Default")
      (node (ref "J22") (pin "2") (pinfunction "2_2") (pintype "passive"))
    )
    (net (code "259") (name "unconnected-(J22-Pad3)") (class "Default")
      (node (ref "J22") (pin "3") (pinfunction "3_3") (pintype "passive"))
    )
    (net (code "260") (name "unconnected-(J22-Pad4)") (class "Default")
      (node (ref "J22") (pin "4") (pinfunction "4_4") (pintype "passive"))
    )
    (net (code "261") (name "unconnected-(J28-Pad1)") (class "Default")
      (node (ref "J28") (pin "1") (pinfunction "1_1") (pintype "passive"))
    )
    (net (code "262") (name "unconnected-(J28-Pad2)") (class "Default")
      (node (ref "J28") (pin "2") (pinfunction "2_2") (pintype "passive"))
    )
    (net (code "263") (name "unconnected-(J28-Pad3)") (class "Default")
      (node (ref "J28") (pin "3") (pinfunction "3_3") (pintype "passive"))
    )
    (net (code "264") (name "unconnected-(J28-Pad4)") (class "Default")
      (node (ref "J28") (pin "4") (pinfunction "4_4") (pintype "passive"))
    )
  )
)
